# PID_Board.net
KiCad netlist of a schematic drawn in EAGLE
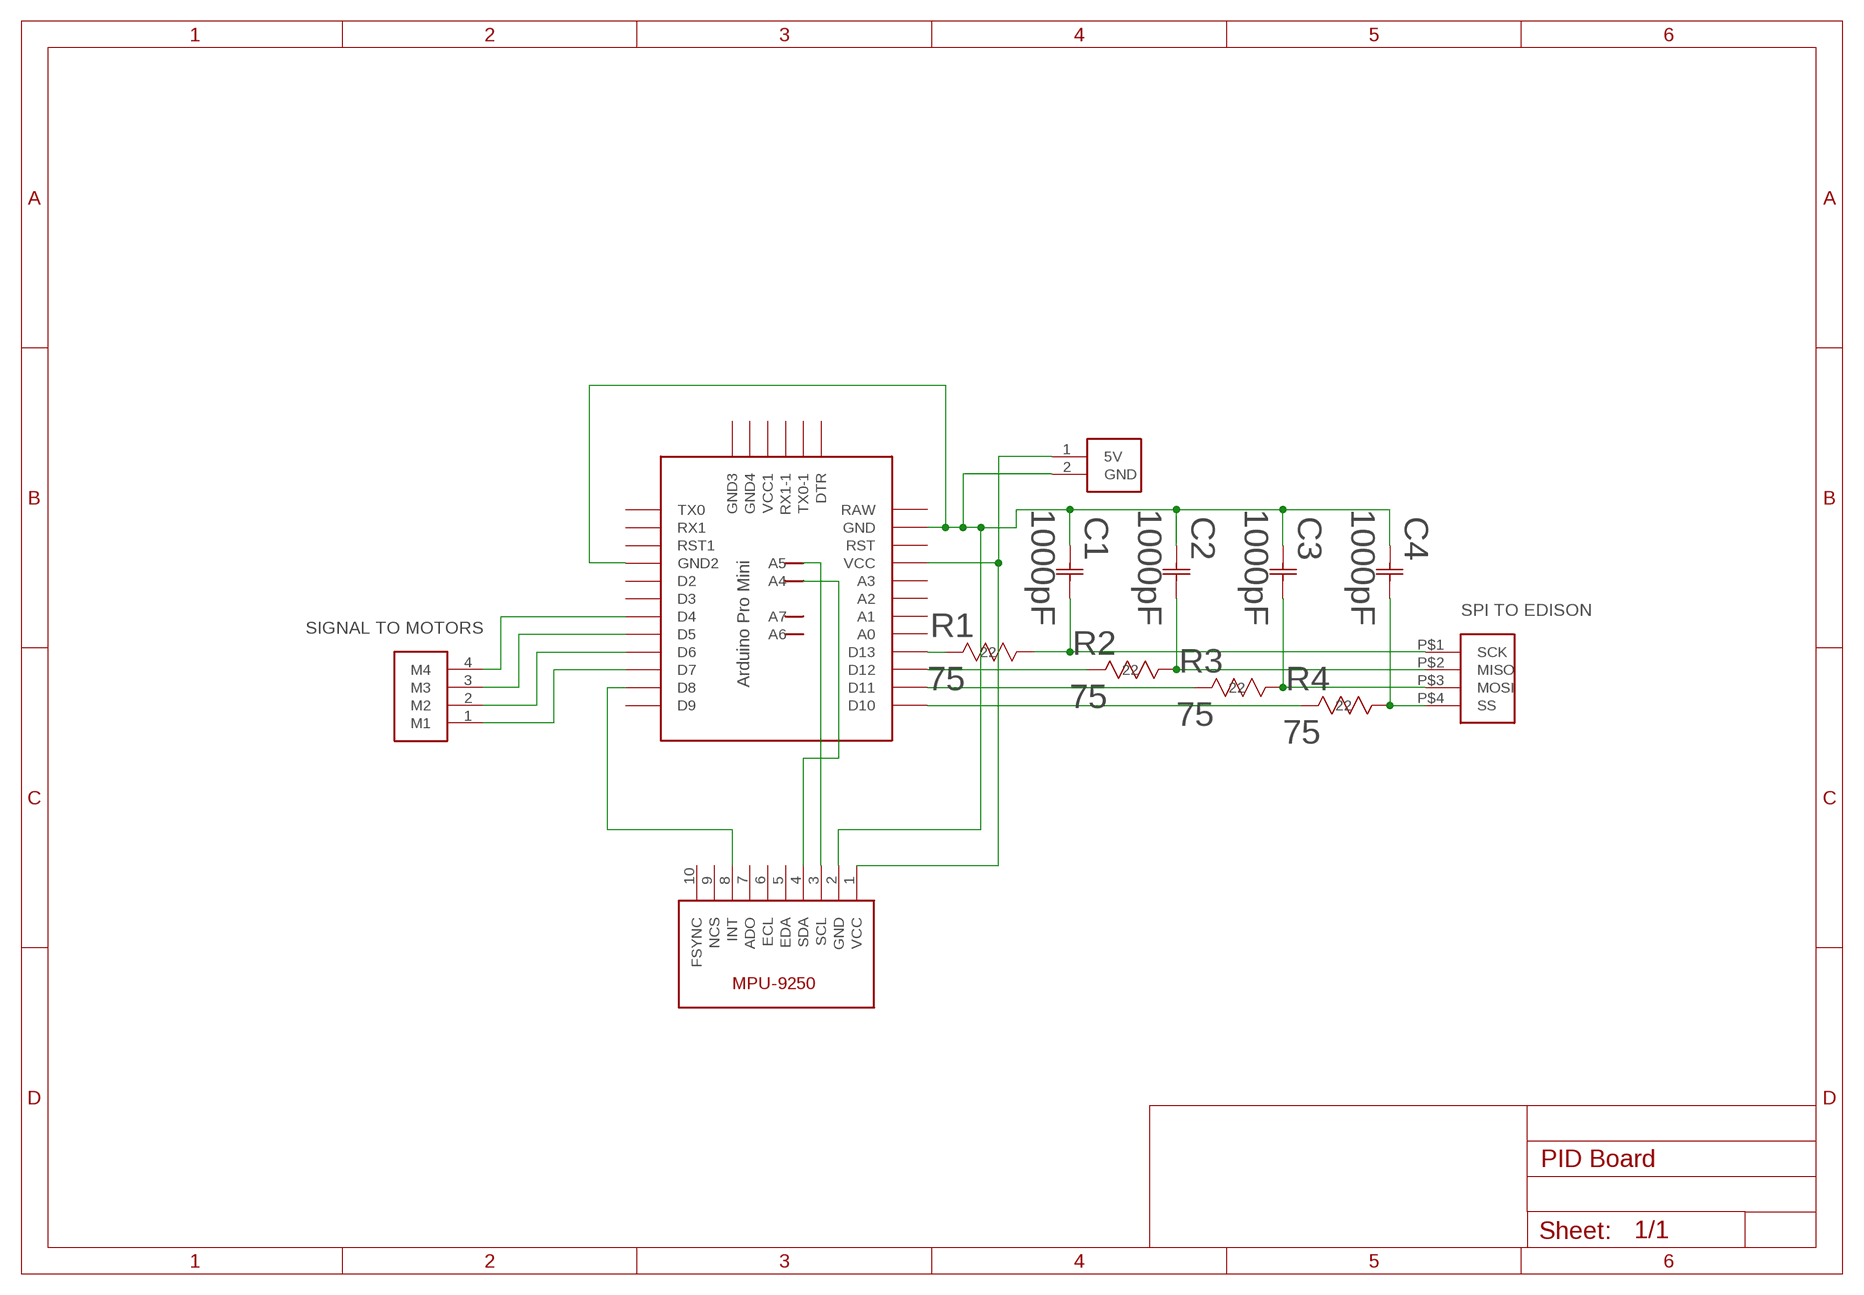
[diagram p0: schematic, sheet 1]

(export (version "E")
  (design (tool "Eeschema 10.0.6"))
  (components
    (comp (ref "C1")
      (value "1000pF")
      (footprint "eagle-import:G-155-M")
      (fields
        (field (name "MANUFACTURER_PART_NUMBER") "GRM155R60J102KA01D")
        (field (name "COPYRIGHT") "Copyright C 2015 Accelerated Designs. All rights reserved")
      )
      (libsource (lib "eagle-import") (part "GRM155R60J102KA01DG-155-M"))
    )
    (comp (ref "C2")
      (value "1000pF")
      (footprint "eagle-import:G-155-M")
      (fields
        (field (name "MANUFACTURER_PART_NUMBER") "GRM155R60J102KA01D")
        (field (name "COPYRIGHT") "Copyright C 2015 Accelerated Designs. All rights reserved")
      )
      (libsource (lib "eagle-import") (part "GRM155R60J102KA01DG-155-M"))
    )
    (comp (ref "C3")
      (value "1000pF")
      (footprint "eagle-import:G-155-M")
      (fields
        (field (name "MANUFACTURER_PART_NUMBER") "GRM155R60J102KA01D")
        (field (name "COPYRIGHT") "Copyright C 2015 Accelerated Designs. All rights reserved")
      )
      (libsource (lib "eagle-import") (part "GRM155R60J102KA01DG-155-M"))
    )
    (comp (ref "C4")
      (value "1000pF")
      (footprint "eagle-import:G-155-M")
      (fields
        (field (name "MANUFACTURER_PART_NUMBER") "GRM155R60J102KA01D")
        (field (name "COPYRIGHT") "Copyright C 2015 Accelerated Designs. All rights reserved")
      )
      (libsource (lib "eagle-import") (part "GRM155R60J102KA01DG-155-M"))
    )
    (comp (ref "J1")
      (value "POWER_CONNECTOR")
      (footprint "eagle-import:XH_CONNECTOR")
      (libsource (lib "eagle-import") (part "POWER_CONNECTOR"))
    )
    (comp (ref "J2")
      (value "SPI_CONNECTOR")
      (footprint "eagle-import:JST-XH_4POS")
      (libsource (lib "eagle-import") (part "SPI_CONNECTOR"))
    )
    (comp (ref "J3")
      (value "4_PIN_CONNECTOR")
      (footprint "eagle-import:4_PIN_CONNECTOR")
      (libsource (lib "eagle-import") (part "4_PIN_CONNECTOR"))
    )
    (comp (ref "R1")
      (value "75")
      (footprint "eagle-import:RC0402N-M")
      (fields
        (field (name "DIGIKEYPARTNUMBER") "31175JRTRND")
        (field (name "MANUFACTURER_PART_NUMBER") "RC0402JR0775RL")
        (field (name "NEWARKPARTNUMBER") "66R1890")
        (field (name "COPYRIGHT") "Copyright C 2015 Accelerated Designs. All rights reserved")
      )
      (libsource (lib "eagle-import") (part "RC0402JR-0775RLRC0402N-M"))
    )
    (comp (ref "R2")
      (value "75")
      (footprint "eagle-import:RC0402N-M")
      (fields
        (field (name "DIGIKEYPARTNUMBER") "31175JRTRND")
        (field (name "MANUFACTURER_PART_NUMBER") "RC0402JR0775RL")
        (field (name "NEWARKPARTNUMBER") "66R1890")
        (field (name "COPYRIGHT") "Copyright C 2015 Accelerated Designs. All rights reserved")
      )
      (libsource (lib "eagle-import") (part "RC0402JR-0775RLRC0402N-M"))
    )
    (comp (ref "R3")
      (value "75")
      (footprint "eagle-import:RC0402N-M")
      (fields
        (field (name "DIGIKEYPARTNUMBER") "31175JRTRND")
        (field (name "MANUFACTURER_PART_NUMBER") "RC0402JR0775RL")
        (field (name "NEWARKPARTNUMBER") "66R1890")
        (field (name "COPYRIGHT") "Copyright C 2015 Accelerated Designs. All rights reserved")
      )
      (libsource (lib "eagle-import") (part "RC0402JR-0775RLRC0402N-M"))
    )
    (comp (ref "R4")
      (value "75")
      (footprint "eagle-import:RC0402N-M")
      (fields
        (field (name "DIGIKEYPARTNUMBER") "31175JRTRND")
        (field (name "MANUFACTURER_PART_NUMBER") "RC0402JR0775RL")
        (field (name "NEWARKPARTNUMBER") "66R1890")
        (field (name "COPYRIGHT") "Copyright C 2015 Accelerated Designs. All rights reserved")
      )
      (libsource (lib "eagle-import") (part "RC0402JR-0775RLRC0402N-M"))
    )
    (comp (ref "U1")
      (value "PRO-MINI-2")
      (footprint "eagle-import:PRO-MINI-2")
      (libsource (lib "eagle-import") (part "PRO-MINI-2"))
    )
    (comp (ref "U2")
      (value "MPU-9250")
      (footprint "eagle-import:MPU-9250")
      (libsource (lib "eagle-import") (part "MPU-9250"))
    )
  )
  (nets
    (net (code "1") (name "Net-(C1-11)") (class "Default")
      (node (ref "C1") (pin "1") (pinfunction "11_1") (pintype "passive"))
      (node (ref "C2") (pin "1") (pinfunction "11_1") (pintype "passive"))
      (node (ref "C3") (pin "1") (pinfunction "11_1") (pintype "passive"))
      (node (ref "C4") (pin "1") (pinfunction "11_1") (pintype "passive"))
      (node (ref "J1") (pin "2") (pinfunction "GND_2") (pintype "power_in"))
      (node (ref "U1") (pin "GND") (pinfunction "GND_GND") (pintype "bidirectional"))
      (node (ref "U1") (pin "GND1") (pinfunction "GND2_GND1") (pintype "bidirectional"))
      (node (ref "U2") (pin "2") (pinfunction "GND_2") (pintype "power_in"))
    )
    (net (code "2") (name "Net-(C1-22)") (class "Default")
      (node (ref "C1") (pin "2") (pinfunction "22_2") (pintype "passive"))
      (node (ref "J2") (pin "P$1") (pinfunction "SCK_P$1") (pintype "bidirectional"))
      (node (ref "R1") (pin "1") (pinfunction "11_1") (pintype "passive"))
    )
    (net (code "3") (name "Net-(C2-22)") (class "Default")
      (node (ref "C2") (pin "2") (pinfunction "22_2") (pintype "passive"))
      (node (ref "J2") (pin "P$2") (pinfunction "MISO_P$2") (pintype "bidirectional"))
      (node (ref "R2") (pin "1") (pinfunction "11_1") (pintype "passive"))
    )
    (net (code "4") (name "Net-(C3-22)") (class "Default")
      (node (ref "C3") (pin "2") (pinfunction "22_2") (pintype "passive"))
      (node (ref "J2") (pin "P$3") (pinfunction "MOSI_P$3") (pintype "bidirectional"))
      (node (ref "R3") (pin "1") (pinfunction "11_1") (pintype "passive"))
    )
    (net (code "5") (name "Net-(C4-22)") (class "Default")
      (node (ref "C4") (pin "2") (pinfunction "22_2") (pintype "passive"))
      (node (ref "J2") (pin "P$4") (pinfunction "SS_P$4") (pintype "bidirectional"))
      (node (ref "R4") (pin "1") (pinfunction "11_1") (pintype "passive"))
    )
    (net (code "6") (name "Net-(J1-5V)") (class "Default")
      (node (ref "J1") (pin "1") (pinfunction "5V_1") (pintype "power_in"))
      (node (ref "U1") (pin "VCC") (pinfunction "VCC_VCC") (pintype "bidirectional"))
      (node (ref "U2") (pin "1") (pinfunction "VCC_1") (pintype "power_in"))
    )
    (net (code "7") (name "Net-(J3-M1)") (class "Default")
      (node (ref "J3") (pin "1") (pinfunction "M1_1") (pintype "bidirectional"))
      (node (ref "U1") (pin "D7") (pinfunction "D7_D7") (pintype "bidirectional"))
    )
    (net (code "8") (name "Net-(J3-M2)") (class "Default")
      (node (ref "J3") (pin "2") (pinfunction "M2_2") (pintype "bidirectional"))
      (node (ref "U1") (pin "D6") (pinfunction "D6_D6") (pintype "bidirectional"))
    )
    (net (code "9") (name "Net-(J3-M3)") (class "Default")
      (node (ref "J3") (pin "3") (pinfunction "M3_3") (pintype "bidirectional"))
      (node (ref "U1") (pin "D5") (pinfunction "D5_D5") (pintype "bidirectional"))
    )
    (net (code "10") (name "Net-(J3-M4)") (class "Default")
      (node (ref "J3") (pin "4") (pinfunction "M4_4") (pintype "bidirectional"))
      (node (ref "U1") (pin "D4") (pinfunction "D4_D4") (pintype "bidirectional"))
    )
    (net (code "11") (name "Net-(R1-22)") (class "Default")
      (node (ref "R1") (pin "2") (pinfunction "22_2") (pintype "passive"))
      (node (ref "U1") (pin "D13") (pinfunction "D13_D13") (pintype "bidirectional"))
    )
    (net (code "12") (name "Net-(R2-22)") (class "Default")
      (node (ref "R2") (pin "2") (pinfunction "22_2") (pintype "passive"))
      (node (ref "U1") (pin "D12") (pinfunction "D12_D12") (pintype "bidirectional"))
    )
    (net (code "13") (name "Net-(R3-22)") (class "Default")
      (node (ref "R3") (pin "2") (pinfunction "22_2") (pintype "passive"))
      (node (ref "U1") (pin "D11") (pinfunction "D11_D11") (pintype "bidirectional"))
    )
    (net (code "14") (name "Net-(R4-22)") (class "Default")
      (node (ref "R4") (pin "2") (pinfunction "22_2") (pintype "passive"))
      (node (ref "U1") (pin "D10") (pinfunction "D10_D10") (pintype "bidirectional"))
    )
    (net (code "15") (name "Net-(U2-INT)") (class "Default")
      (node (ref "U1") (pin "D8") (pinfunction "D8_D8") (pintype "bidirectional"))
      (node (ref "U2") (pin "8") (pinfunction "INT_8") (pintype "bidirectional"))
    )
    (net (code "16") (name "Net-(U2-SCL)") (class "Default")
      (node (ref "U1") (pin "A5") (pinfunction "A5_A5") (pintype "bidirectional"))
      (node (ref "U2") (pin "3") (pinfunction "SCL_3") (pintype "bidirectional"))
    )
    (net (code "17") (name "Net-(U2-SDA)") (class "Default")
      (node (ref "U1") (pin "A4") (pinfunction "A4_A4") (pintype "bidirectional"))
      (node (ref "U2") (pin "4") (pinfunction "SDA_4") (pintype "bidirectional"))
    )
    (net (code "18") (name "unconnected-(U1-GND3-PadGND2)") (class "Default")
      (node (ref "U1") (pin "GND2") (pinfunction "GND3_GND2") (pintype "bidirectional"))
    )
    (net (code "19") (name "unconnected-(U1-GND4-PadGND3)") (class "Default")
      (node (ref "U1") (pin "GND3") (pinfunction "GND4_GND3") (pintype "bidirectional"))
    )
    (net (code "20") (name "unconnected-(U1-PadA0)") (class "Default")
      (node (ref "U1") (pin "A0") (pinfunction "A0_A0") (pintype "bidirectional"))
    )
    (net (code "21") (name "unconnected-(U1-PadA1)") (class "Default")
      (node (ref "U1") (pin "A1") (pinfunction "A1_A1") (pintype "bidirectional"))
    )
    (net (code "22") (name "unconnected-(U1-PadA2)") (class "Default")
      (node (ref "U1") (pin "A2") (pinfunction "A2_A2") (pintype "bidirectional"))
    )
    (net (code "23") (name "unconnected-(U1-PadA3)") (class "Default")
      (node (ref "U1") (pin "A3") (pinfunction "A3_A3") (pintype "bidirectional"))
    )
    (net (code "24") (name "unconnected-(U1-PadA6)") (class "Default")
      (node (ref "U1") (pin "A6") (pinfunction "A6_A6") (pintype "bidirectional"))
    )
    (net (code "25") (name "unconnected-(U1-PadA7)") (class "Default")
      (node (ref "U1") (pin "A7") (pinfunction "A7_A7") (pintype "bidirectional"))
    )
    (net (code "26") (name "unconnected-(U1-PadD2)") (class "Default")
      (node (ref "U1") (pin "D2") (pinfunction "D2_D2") (pintype "bidirectional"))
    )
    (net (code "27") (name "unconnected-(U1-PadD3)") (class "Default")
      (node (ref "U1") (pin "D3") (pinfunction "D3_D3") (pintype "bidirectional"))
    )
    (net (code "28") (name "unconnected-(U1-PadD9)") (class "Default")
      (node (ref "U1") (pin "D9") (pinfunction "D9_D9") (pintype "bidirectional"))
    )
    (net (code "29") (name "unconnected-(U1-PadDTR)") (class "Default")
      (node (ref "U1") (pin "DTR") (pinfunction "DTR_DTR") (pintype "bidirectional"))
    )
    (net (code "30") (name "unconnected-(U1-PadRAW)") (class "Default")
      (node (ref "U1") (pin "RAW") (pinfunction "RAW_RAW") (pintype "bidirectional"))
    )
    (net (code "31") (name "unconnected-(U1-PadRST)") (class "Default")
      (node (ref "U1") (pin "RST") (pinfunction "RST_RST") (pintype "bidirectional"))
    )
    (net (code "32") (name "unconnected-(U1-PadRST1)") (class "Default")
      (node (ref "U1") (pin "RST1") (pinfunction "RST1_RST1") (pintype "bidirectional"))
    )
    (net (code "33") (name "unconnected-(U1-PadRX1)") (class "Default")
      (node (ref "U1") (pin "RX1") (pinfunction "RX1_RX1") (pintype "bidirectional"))
    )
    (net (code "34") (name "unconnected-(U1-PadRX1-1)") (class "Default")
      (node (ref "U1") (pin "RX1-1") (pinfunction "RX1-1_RX1-1") (pintype "bidirectional"))
    )
    (net (code "35") (name "unconnected-(U1-PadTX0)") (class "Default")
      (node (ref "U1") (pin "TX0") (pinfunction "TX0_TX0") (pintype "bidirectional"))
    )
    (net (code "36") (name "unconnected-(U1-PadTX0-1)") (class "Default")
      (node (ref "U1") (pin "TX0-1") (pinfunction "TX0-1_TX0-1") (pintype "bidirectional"))
    )
    (net (code "37") (name "unconnected-(U1-PadVCC1)") (class "Default")
      (node (ref "U1") (pin "VCC1") (pinfunction "VCC1_VCC1") (pintype "bidirectional"))
    )
    (net (code "38") (name "unconnected-(U2-ADO-Pad7)") (class "Default")
      (node (ref "U2") (pin "7") (pinfunction "ADO_7") (pintype "bidirectional"))
    )
    (net (code "39") (name "unconnected-(U2-ECL-Pad6)") (class "Default")
      (node (ref "U2") (pin "6") (pinfunction "ECL_6") (pintype "bidirectional"))
    )
    (net (code "40") (name "unconnected-(U2-EDA-Pad5)") (class "Default")
      (node (ref "U2") (pin "5") (pinfunction "EDA_5") (pintype "bidirectional"))
    )
    (net (code "41") (name "unconnected-(U2-FSYNC-Pad10)") (class "Default")
      (node (ref "U2") (pin "10") (pinfunction "FSYNC_10") (pintype "bidirectional"))
    )
    (net (code "42") (name "unconnected-(U2-NCS-Pad9)") (class "Default")
      (node (ref "U2") (pin "9") (pinfunction "NCS_9") (pintype "bidirectional"))
    )
  )
)
